# SparkyJrRemorandumExpansion.net
KiCad netlist of a schematic drawn in EAGLE
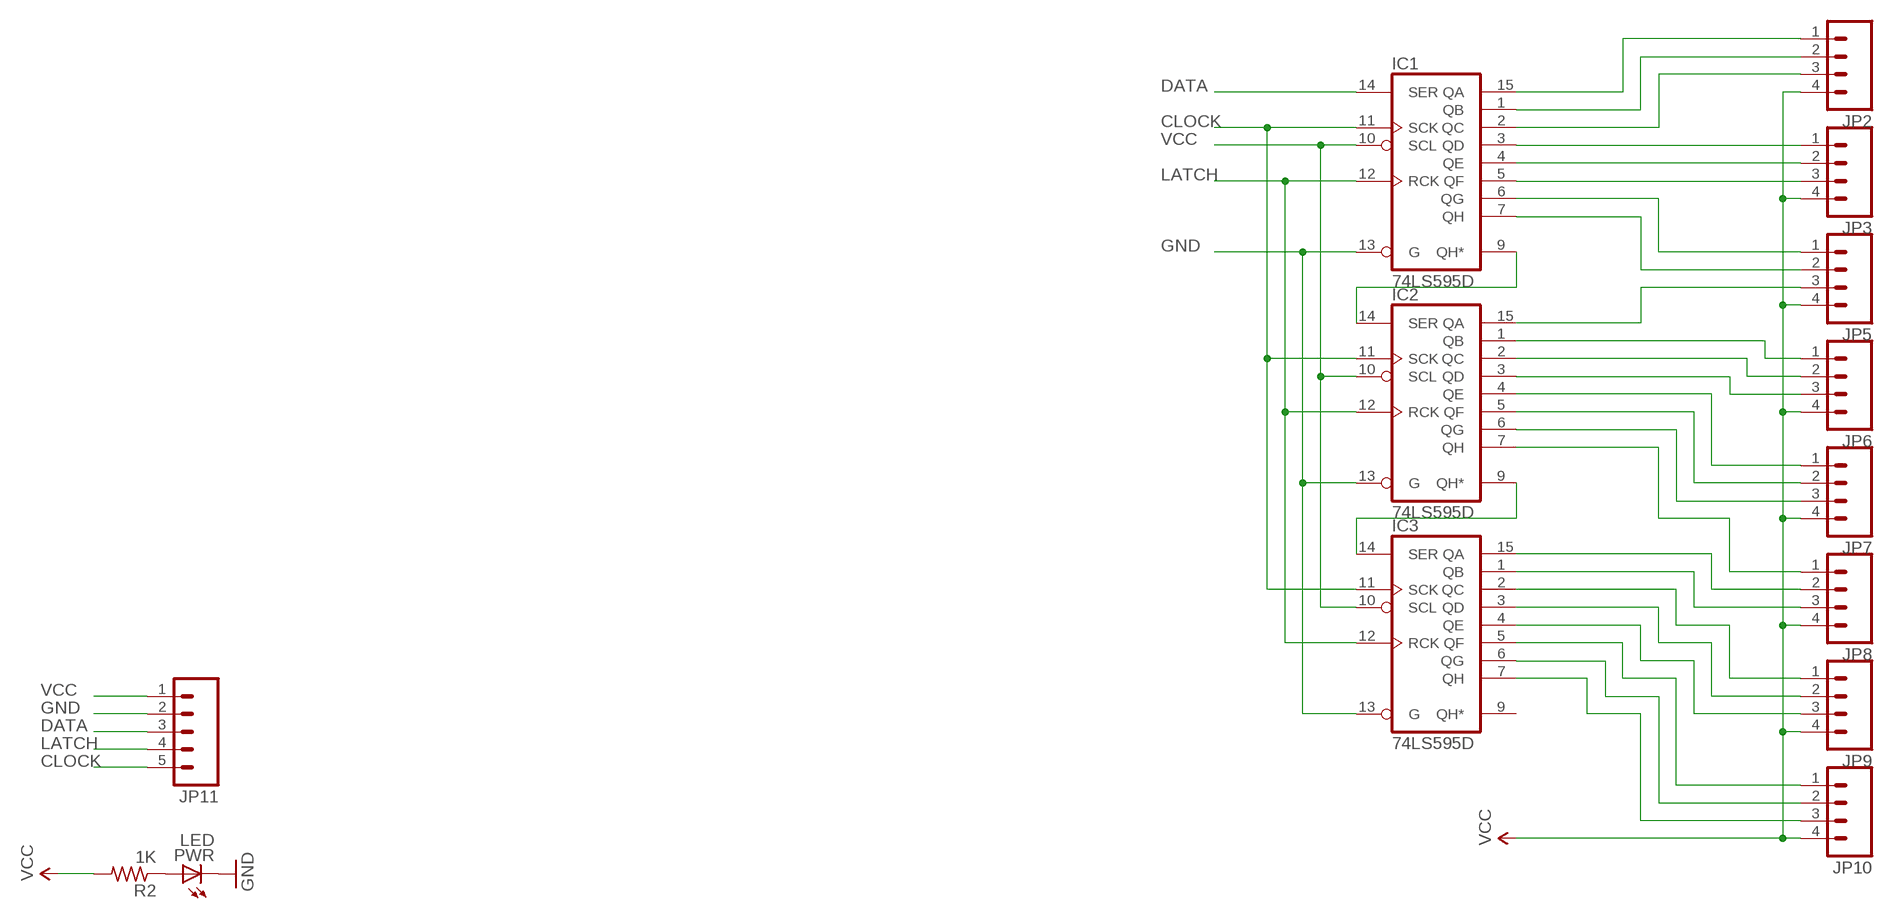
[diagram p0: schematic, sheet 1]

(export (version "E")
  (design (tool "Eeschema 10.0.6"))
  (components
    (comp (ref "IC1")
      (value "74LS595D")
      (footprint "eagle-import:SO16")
      (libsource (lib "eagle-import") (part "74595DLS"))
    )
    (comp (ref "IC2")
      (value "74LS595D")
      (footprint "eagle-import:SO16")
      (libsource (lib "eagle-import") (part "74595DLS"))
    )
    (comp (ref "IC3")
      (value "74LS595D")
      (footprint "eagle-import:SO16")
      (libsource (lib "eagle-import") (part "74595DLS"))
    )
    (comp (ref "JP2")
      (value "M04PTH")
      (footprint "eagle-import:1X04")
      (libsource (lib "eagle-import") (part "M04PTH"))
    )
    (comp (ref "JP3")
      (value "M04PTH")
      (footprint "eagle-import:1X04")
      (libsource (lib "eagle-import") (part "M04PTH"))
    )
    (comp (ref "JP5")
      (value "M04PTH")
      (footprint "eagle-import:1X04")
      (libsource (lib "eagle-import") (part "M04PTH"))
    )
    (comp (ref "JP6")
      (value "M04PTH")
      (footprint "eagle-import:1X04")
      (libsource (lib "eagle-import") (part "M04PTH"))
    )
    (comp (ref "JP7")
      (value "M04PTH")
      (footprint "eagle-import:1X04")
      (libsource (lib "eagle-import") (part "M04PTH"))
    )
    (comp (ref "JP8")
      (value "M04PTH")
      (footprint "eagle-import:1X04")
      (libsource (lib "eagle-import") (part "M04PTH"))
    )
    (comp (ref "JP9")
      (value "M04PTH")
      (footprint "eagle-import:1X04")
      (libsource (lib "eagle-import") (part "M04PTH"))
    )
    (comp (ref "JP10")
      (value "M04PTH")
      (footprint "eagle-import:1X04")
      (libsource (lib "eagle-import") (part "M04PTH"))
    )
    (comp (ref "JP11")
      (value "M05PTH")
      (footprint "eagle-import:1X05")
      (libsource (lib "eagle-import") (part "M05PTH"))
    )
    (comp (ref "PWR")
      (value "LED")
      (footprint "eagle-import:CHIPLED_0805")
      (libsource (lib "eagle-import") (part "LEDCHIPLED_0805"))
    )
    (comp (ref "R2")
      (value "1K")
      (footprint "eagle-import:R0805")
      (libsource (lib "eagle-import") (part "R-US_R0805"))
    )
  )
  (nets
    (net (code "1") (name "/CLOCK") (class "Default")
      (node (ref "IC1") (pin "11") (pinfunction "SCK_11") (pintype "input"))
      (node (ref "IC2") (pin "11") (pinfunction "SCK_11") (pintype "input"))
      (node (ref "IC3") (pin "11") (pinfunction "SCK_11") (pintype "input"))
      (node (ref "JP11") (pin "5") (pinfunction "5_5") (pintype "passive"))
    )
    (net (code "2") (name "/DATA") (class "Default")
      (node (ref "IC1") (pin "14") (pinfunction "SER_14") (pintype "input"))
      (node (ref "JP11") (pin "3") (pinfunction "3_3") (pintype "passive"))
    )
    (net (code "3") (name "/LATCH") (class "Default")
      (node (ref "IC1") (pin "12") (pinfunction "RCK_12") (pintype "input"))
      (node (ref "IC2") (pin "12") (pinfunction "RCK_12") (pintype "input"))
      (node (ref "IC3") (pin "12") (pinfunction "RCK_12") (pintype "input"))
      (node (ref "JP11") (pin "4") (pinfunction "4_4") (pintype "passive"))
    )
    (net (code "4") (name "GND") (class "Default")
      (node (ref "IC1") (pin "13") (pinfunction "G_13") (pintype "input"))
      (node (ref "IC2") (pin "13") (pinfunction "G_13") (pintype "input"))
      (node (ref "IC3") (pin "13") (pinfunction "G_13") (pintype "input"))
      (node (ref "JP11") (pin "2") (pinfunction "2_2") (pintype "passive"))
      (node (ref "PWR") (pin "C") (pinfunction "C_C") (pintype "passive"))
    )
    (net (code "5") (name "Net-(IC1A-QA)") (class "Default")
      (node (ref "IC1") (pin "15") (pinfunction "QA_15") (pintype "tri_state"))
      (node (ref "JP2") (pin "1") (pinfunction "1_1") (pintype "passive"))
    )
    (net (code "6") (name "Net-(IC1A-QB)") (class "Default")
      (node (ref "IC1") (pin "1") (pinfunction "QB_1") (pintype "tri_state"))
      (node (ref "JP2") (pin "2") (pinfunction "2_2") (pintype "passive"))
    )
    (net (code "7") (name "Net-(IC1A-QC)") (class "Default")
      (node (ref "IC1") (pin "2") (pinfunction "QC_2") (pintype "tri_state"))
      (node (ref "JP2") (pin "3") (pinfunction "3_3") (pintype "passive"))
    )
    (net (code "8") (name "Net-(IC1A-QD)") (class "Default")
      (node (ref "IC1") (pin "3") (pinfunction "QD_3") (pintype "tri_state"))
      (node (ref "JP3") (pin "1") (pinfunction "1_1") (pintype "passive"))
    )
    (net (code "9") (name "Net-(IC1A-QE)") (class "Default")
      (node (ref "IC1") (pin "4") (pinfunction "QE_4") (pintype "tri_state"))
      (node (ref "JP3") (pin "2") (pinfunction "2_2") (pintype "passive"))
    )
    (net (code "10") (name "Net-(IC1A-QF)") (class "Default")
      (node (ref "IC1") (pin "5") (pinfunction "QF_5") (pintype "tri_state"))
      (node (ref "JP3") (pin "3") (pinfunction "3_3") (pintype "passive"))
    )
    (net (code "11") (name "Net-(IC1A-QG)") (class "Default")
      (node (ref "IC1") (pin "6") (pinfunction "QG_6") (pintype "tri_state"))
      (node (ref "JP5") (pin "1") (pinfunction "1_1") (pintype "passive"))
    )
    (net (code "12") (name "Net-(IC1A-QH)") (class "Default")
      (node (ref "IC1") (pin "7") (pinfunction "QH_7") (pintype "tri_state"))
      (node (ref "JP5") (pin "2") (pinfunction "2_2") (pintype "passive"))
    )
    (net (code "13") (name "Net-(IC1A-QH*)") (class "Default")
      (node (ref "IC1") (pin "9") (pinfunction "QH*_9") (pintype "tri_state"))
      (node (ref "IC2") (pin "14") (pinfunction "SER_14") (pintype "input"))
    )
    (net (code "14") (name "Net-(IC2A-QA)") (class "Default")
      (node (ref "IC2") (pin "15") (pinfunction "QA_15") (pintype "tri_state"))
      (node (ref "JP5") (pin "3") (pinfunction "3_3") (pintype "passive"))
    )
    (net (code "15") (name "Net-(IC2A-QB)") (class "Default")
      (node (ref "IC2") (pin "1") (pinfunction "QB_1") (pintype "tri_state"))
      (node (ref "JP6") (pin "1") (pinfunction "1_1") (pintype "passive"))
    )
    (net (code "16") (name "Net-(IC2A-QC)") (class "Default")
      (node (ref "IC2") (pin "2") (pinfunction "QC_2") (pintype "tri_state"))
      (node (ref "JP6") (pin "2") (pinfunction "2_2") (pintype "passive"))
    )
    (net (code "17") (name "Net-(IC2A-QD)") (class "Default")
      (node (ref "IC2") (pin "3") (pinfunction "QD_3") (pintype "tri_state"))
      (node (ref "JP6") (pin "3") (pinfunction "3_3") (pintype "passive"))
    )
    (net (code "18") (name "Net-(IC2A-QE)") (class "Default")
      (node (ref "IC2") (pin "4") (pinfunction "QE_4") (pintype "tri_state"))
      (node (ref "JP7") (pin "1") (pinfunction "1_1") (pintype "passive"))
    )
    (net (code "19") (name "Net-(IC2A-QF)") (class "Default")
      (node (ref "IC2") (pin "5") (pinfunction "QF_5") (pintype "tri_state"))
      (node (ref "JP7") (pin "2") (pinfunction "2_2") (pintype "passive"))
    )
    (net (code "20") (name "Net-(IC2A-QG)") (class "Default")
      (node (ref "IC2") (pin "6") (pinfunction "QG_6") (pintype "tri_state"))
      (node (ref "JP7") (pin "3") (pinfunction "3_3") (pintype "passive"))
    )
    (net (code "21") (name "Net-(IC2A-QH)") (class "Default")
      (node (ref "IC2") (pin "7") (pinfunction "QH_7") (pintype "tri_state"))
      (node (ref "JP8") (pin "1") (pinfunction "1_1") (pintype "passive"))
    )
    (net (code "22") (name "Net-(IC2A-QH*)") (class "Default")
      (node (ref "IC2") (pin "9") (pinfunction "QH*_9") (pintype "tri_state"))
      (node (ref "IC3") (pin "14") (pinfunction "SER_14") (pintype "input"))
    )
    (net (code "23") (name "Net-(IC3A-QA)") (class "Default")
      (node (ref "IC3") (pin "15") (pinfunction "QA_15") (pintype "tri_state"))
      (node (ref "JP8") (pin "2") (pinfunction "2_2") (pintype "passive"))
    )
    (net (code "24") (name "Net-(IC3A-QB)") (class "Default")
      (node (ref "IC3") (pin "1") (pinfunction "QB_1") (pintype "tri_state"))
      (node (ref "JP8") (pin "3") (pinfunction "3_3") (pintype "passive"))
    )
    (net (code "25") (name "Net-(IC3A-QC)") (class "Default")
      (node (ref "IC3") (pin "2") (pinfunction "QC_2") (pintype "tri_state"))
      (node (ref "JP9") (pin "1") (pinfunction "1_1") (pintype "passive"))
    )
    (net (code "26") (name "Net-(IC3A-QD)") (class "Default")
      (node (ref "IC3") (pin "3") (pinfunction "QD_3") (pintype "tri_state"))
      (node (ref "JP9") (pin "2") (pinfunction "2_2") (pintype "passive"))
    )
    (net (code "27") (name "Net-(IC3A-QE)") (class "Default")
      (node (ref "IC3") (pin "4") (pinfunction "QE_4") (pintype "tri_state"))
      (node (ref "JP9") (pin "3") (pinfunction "3_3") (pintype "passive"))
    )
    (net (code "28") (name "Net-(IC3A-QF)") (class "Default")
      (node (ref "IC3") (pin "5") (pinfunction "QF_5") (pintype "tri_state"))
      (node (ref "JP10") (pin "1") (pinfunction "1_1") (pintype "passive"))
    )
    (net (code "29") (name "Net-(IC3A-QG)") (class "Default")
      (node (ref "IC3") (pin "6") (pinfunction "QG_6") (pintype "tri_state"))
      (node (ref "JP10") (pin "2") (pinfunction "2_2") (pintype "passive"))
    )
    (net (code "30") (name "Net-(IC3A-QH)") (class "Default")
      (node (ref "IC3") (pin "7") (pinfunction "QH_7") (pintype "tri_state"))
      (node (ref "JP10") (pin "3") (pinfunction "3_3") (pintype "passive"))
    )
    (net (code "31") (name "Net-(PWR-PadA)") (class "Default")
      (node (ref "PWR") (pin "A") (pinfunction "A_A") (pintype "passive"))
      (node (ref "R2") (pin "1") (pinfunction "1_1") (pintype "passive"))
    )
    (net (code "32") (name "VCC") (class "Default")
      (node (ref "IC1") (pin "10") (pinfunction "SCL_10") (pintype "input"))
      (node (ref "IC2") (pin "10") (pinfunction "SCL_10") (pintype "input"))
      (node (ref "IC3") (pin "10") (pinfunction "SCL_10") (pintype "input"))
      (node (ref "JP10") (pin "4") (pinfunction "4_4") (pintype "passive"))
      (node (ref "JP11") (pin "1") (pinfunction "1_1") (pintype "passive"))
      (node (ref "JP2") (pin "4") (pinfunction "4_4") (pintype "passive"))
      (node (ref "JP3") (pin "4") (pinfunction "4_4") (pintype "passive"))
      (node (ref "JP5") (pin "4") (pinfunction "4_4") (pintype "passive"))
      (node (ref "JP6") (pin "4") (pinfunction "4_4") (pintype "passive"))
      (node (ref "JP7") (pin "4") (pinfunction "4_4") (pintype "passive"))
      (node (ref "JP8") (pin "4") (pinfunction "4_4") (pintype "passive"))
      (node (ref "JP9") (pin "4") (pinfunction "4_4") (pintype "passive"))
      (node (ref "R2") (pin "2") (pinfunction "2_2") (pintype "passive"))
    )
    (net (code "33") (name "unconnected-(IC3A-QH*-Pad9)") (class "Default")
      (node (ref "IC3") (pin "9") (pinfunction "QH*_9") (pintype "tri_state"))
    )
  )
)
